# Controller.net
KiCad netlist of a schematic drawn in EAGLE
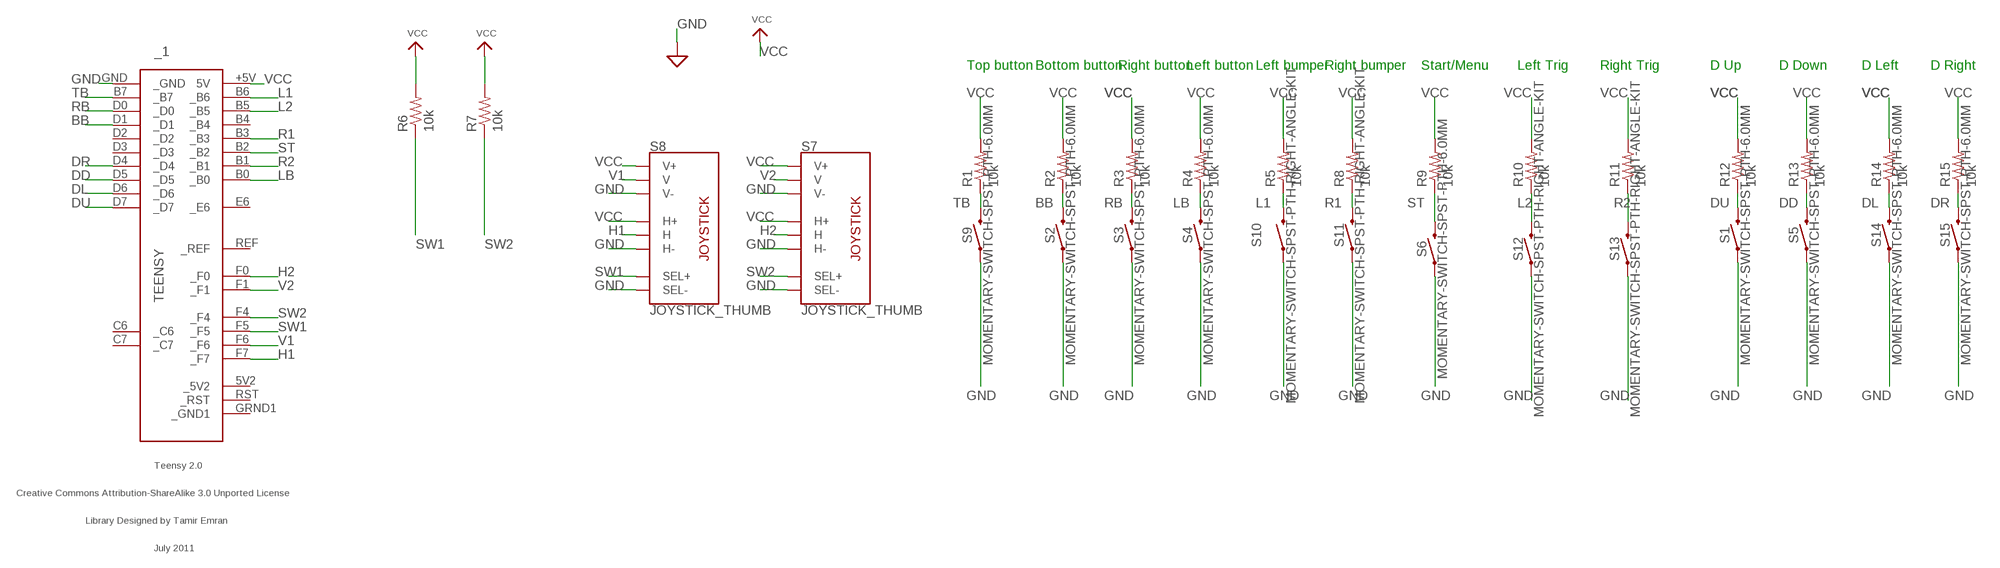
[diagram p0: schematic, sheet 1]

(export (version "E")
  (design (tool "Eeschema 10.0.6"))
  (components
    (comp (ref "R1")
      (value "10k")
      (footprint "eagle-import:0207_10")
      (libsource (lib "eagle-import") (part "R-US_0207/10"))
    )
    (comp (ref "R2")
      (value "10k")
      (footprint "eagle-import:0207_10")
      (libsource (lib "eagle-import") (part "R-US_0207/10"))
    )
    (comp (ref "R3")
      (value "10k")
      (footprint "eagle-import:0207_10")
      (libsource (lib "eagle-import") (part "R-US_0207/10"))
    )
    (comp (ref "R4")
      (value "10k")
      (footprint "eagle-import:0207_10")
      (libsource (lib "eagle-import") (part "R-US_0207/10"))
    )
    (comp (ref "R5")
      (value "10k")
      (footprint "eagle-import:0207_10")
      (libsource (lib "eagle-import") (part "R-US_0207/10"))
    )
    (comp (ref "R6")
      (value "10k")
      (footprint "eagle-import:0207_10")
      (libsource (lib "eagle-import") (part "R-US_0207/10"))
    )
    (comp (ref "R7")
      (value "10k")
      (footprint "eagle-import:0207_10")
      (libsource (lib "eagle-import") (part "R-US_0207/10"))
    )
    (comp (ref "R8")
      (value "10k")
      (footprint "eagle-import:0207_10")
      (libsource (lib "eagle-import") (part "R-US_0207/10"))
    )
    (comp (ref "R9")
      (value "10k")
      (footprint "eagle-import:0207_10")
      (libsource (lib "eagle-import") (part "R-US_0207/10"))
    )
    (comp (ref "R10")
      (value "10k")
      (footprint "eagle-import:0207_10")
      (libsource (lib "eagle-import") (part "R-US_0207/10"))
    )
    (comp (ref "R11")
      (value "10k")
      (footprint "eagle-import:0207_10")
      (libsource (lib "eagle-import") (part "R-US_0207/10"))
    )
    (comp (ref "R12")
      (value "10k")
      (footprint "eagle-import:0207_10")
      (libsource (lib "eagle-import") (part "R-US_0207/10"))
    )
    (comp (ref "R13")
      (value "10k")
      (footprint "eagle-import:0207_10")
      (libsource (lib "eagle-import") (part "R-US_0207/10"))
    )
    (comp (ref "R14")
      (value "10k")
      (footprint "eagle-import:0207_10")
      (libsource (lib "eagle-import") (part "R-US_0207/10"))
    )
    (comp (ref "R15")
      (value "10k")
      (footprint "eagle-import:0207_10")
      (libsource (lib "eagle-import") (part "R-US_0207/10"))
    )
    (comp (ref "S1")
      (value "MOMENTARY-SWITCH-SPST-PTH-6.0MM")
      (footprint "eagle-import:TACTILE_SWITCH_PTH_6.0MM")
      (libsource (lib "eagle-import") (part "MOMENTARY-SWITCH-SPST-PTH-6.0MM"))
    )
    (comp (ref "S2")
      (value "MOMENTARY-SWITCH-SPST-PTH-6.0MM")
      (footprint "eagle-import:TACTILE_SWITCH_PTH_6.0MM")
      (libsource (lib "eagle-import") (part "MOMENTARY-SWITCH-SPST-PTH-6.0MM"))
    )
    (comp (ref "S3")
      (value "MOMENTARY-SWITCH-SPST-PTH-6.0MM")
      (footprint "eagle-import:TACTILE_SWITCH_PTH_6.0MM")
      (libsource (lib "eagle-import") (part "MOMENTARY-SWITCH-SPST-PTH-6.0MM"))
    )
    (comp (ref "S4")
      (value "MOMENTARY-SWITCH-SPST-PTH-6.0MM")
      (footprint "eagle-import:TACTILE_SWITCH_PTH_6.0MM")
      (libsource (lib "eagle-import") (part "MOMENTARY-SWITCH-SPST-PTH-6.0MM"))
    )
    (comp (ref "S5")
      (value "MOMENTARY-SWITCH-SPST-PTH-6.0MM")
      (footprint "eagle-import:TACTILE_SWITCH_PTH_6.0MM")
      (libsource (lib "eagle-import") (part "MOMENTARY-SWITCH-SPST-PTH-6.0MM"))
    )
    (comp (ref "S6")
      (value "MOMENTARY-SWITCH-SPST-PTH-6.0MM")
      (footprint "eagle-import:TACTILE_SWITCH_PTH_6.0MM")
      (libsource (lib "eagle-import") (part "MOMENTARY-SWITCH-SPST-PTH-6.0MM"))
    )
    (comp (ref "S7")
      (value "JOYSTICK_THUMB")
      (footprint "eagle-import:JOYSTICK")
      (libsource (lib "eagle-import") (part "JOYSTICK_THUMB"))
    )
    (comp (ref "S8")
      (value "JOYSTICK_THUMB")
      (footprint "eagle-import:JOYSTICK")
      (libsource (lib "eagle-import") (part "JOYSTICK_THUMB"))
    )
    (comp (ref "S9")
      (value "MOMENTARY-SWITCH-SPST-PTH-6.0MM")
      (footprint "eagle-import:TACTILE_SWITCH_PTH_6.0MM")
      (libsource (lib "eagle-import") (part "MOMENTARY-SWITCH-SPST-PTH-6.0MM"))
    )
    (comp (ref "S10")
      (value "MOMENTARY-SWITCH-SPST-PTH-RIGHT-ANGLE-KIT")
      (footprint "eagle-import:TACTILE_SWITCH_PTH_RIGHT_ANGLE_KIT")
      (libsource (lib "eagle-import") (part "MOMENTARY-SWITCH-SPST-PTH-RIGHT-ANGLE-KIT"))
    )
    (comp (ref "S11")
      (value "MOMENTARY-SWITCH-SPST-PTH-RIGHT-ANGLE-KIT")
      (footprint "eagle-import:TACTILE_SWITCH_PTH_RIGHT_ANGLE_KIT")
      (libsource (lib "eagle-import") (part "MOMENTARY-SWITCH-SPST-PTH-RIGHT-ANGLE-KIT"))
    )
    (comp (ref "S12")
      (value "MOMENTARY-SWITCH-SPST-PTH-RIGHT-ANGLE-KIT")
      (footprint "eagle-import:TACTILE_SWITCH_PTH_RIGHT_ANGLE_KIT")
      (libsource (lib "eagle-import") (part "MOMENTARY-SWITCH-SPST-PTH-RIGHT-ANGLE-KIT"))
    )
    (comp (ref "S13")
      (value "MOMENTARY-SWITCH-SPST-PTH-RIGHT-ANGLE-KIT")
      (footprint "eagle-import:TACTILE_SWITCH_PTH_RIGHT_ANGLE_KIT")
      (libsource (lib "eagle-import") (part "MOMENTARY-SWITCH-SPST-PTH-RIGHT-ANGLE-KIT"))
    )
    (comp (ref "S14")
      (value "MOMENTARY-SWITCH-SPST-PTH-6.0MM")
      (footprint "eagle-import:TACTILE_SWITCH_PTH_6.0MM")
      (libsource (lib "eagle-import") (part "MOMENTARY-SWITCH-SPST-PTH-6.0MM"))
    )
    (comp (ref "S15")
      (value "MOMENTARY-SWITCH-SPST-PTH-6.0MM")
      (footprint "eagle-import:TACTILE_SWITCH_PTH_6.0MM")
      (libsource (lib "eagle-import") (part "MOMENTARY-SWITCH-SPST-PTH-6.0MM"))
    )
    (comp (ref "_1")
      (value "TEENSY")
      (footprint "eagle-import:TEENSY")
      (libsource (lib "eagle-import") (part "TEENSY"))
    )
  )
  (nets
    (net (code "1") (name "/BB") (class "Default")
      (node (ref "R2") (pin "1") (pinfunction "1_1") (pintype "passive"))
      (node (ref "S2") (pin "3") (pinfunction "2_3") (pintype "passive"))
      (node (ref "_1") (pin "D1") (pinfunction "_D1_D1") (pintype "bidirectional"))
    )
    (net (code "2") (name "/DD") (class "Default")
      (node (ref "R13") (pin "1") (pinfunction "1_1") (pintype "passive"))
      (node (ref "S5") (pin "3") (pinfunction "2_3") (pintype "passive"))
      (node (ref "_1") (pin "D5") (pinfunction "_D5_D5") (pintype "bidirectional"))
    )
    (net (code "3") (name "/DL") (class "Default")
      (node (ref "R14") (pin "1") (pinfunction "1_1") (pintype "passive"))
      (node (ref "S14") (pin "3") (pinfunction "2_3") (pintype "passive"))
      (node (ref "_1") (pin "D6") (pinfunction "_D6_D6") (pintype "bidirectional"))
    )
    (net (code "4") (name "/DR") (class "Default")
      (node (ref "R15") (pin "1") (pinfunction "1_1") (pintype "passive"))
      (node (ref "S15") (pin "3") (pinfunction "2_3") (pintype "passive"))
      (node (ref "_1") (pin "D4") (pinfunction "_D4_D4") (pintype "bidirectional"))
    )
    (net (code "5") (name "/DU") (class "Default")
      (node (ref "R12") (pin "1") (pinfunction "1_1") (pintype "passive"))
      (node (ref "S1") (pin "3") (pinfunction "2_3") (pintype "passive"))
      (node (ref "_1") (pin "D7") (pinfunction "_D7_D7") (pintype "bidirectional"))
    )
    (net (code "6") (name "/H1") (class "Default")
      (node (ref "S8") (pin "H2") (pinfunction "H_H2") (pintype "bidirectional"))
      (node (ref "_1") (pin "F7") (pinfunction "_F7_F7") (pintype "bidirectional"))
    )
    (net (code "7") (name "/H2") (class "Default")
      (node (ref "S7") (pin "H2") (pinfunction "H_H2") (pintype "bidirectional"))
      (node (ref "_1") (pin "F0") (pinfunction "_F0_F0") (pintype "bidirectional"))
    )
    (net (code "8") (name "/L1") (class "Default")
      (node (ref "R5") (pin "1") (pinfunction "1_1") (pintype "passive"))
      (node (ref "S10") (pin "2") (pinfunction "2_2") (pintype "passive"))
      (node (ref "_1") (pin "B6") (pinfunction "_B6_B6") (pintype "bidirectional"))
    )
    (net (code "9") (name "/L2") (class "Default")
      (node (ref "R10") (pin "1") (pinfunction "1_1") (pintype "passive"))
      (node (ref "S12") (pin "2") (pinfunction "2_2") (pintype "passive"))
      (node (ref "_1") (pin "B5") (pinfunction "_B5_B5") (pintype "bidirectional"))
    )
    (net (code "10") (name "/LB") (class "Default")
      (node (ref "R4") (pin "1") (pinfunction "1_1") (pintype "passive"))
      (node (ref "S4") (pin "3") (pinfunction "2_3") (pintype "passive"))
      (node (ref "_1") (pin "B0") (pinfunction "_B0_B0") (pintype "bidirectional"))
    )
    (net (code "11") (name "/R1") (class "Default")
      (node (ref "R8") (pin "1") (pinfunction "1_1") (pintype "passive"))
      (node (ref "S11") (pin "2") (pinfunction "2_2") (pintype "passive"))
      (node (ref "_1") (pin "B3") (pinfunction "_B3_B3") (pintype "bidirectional"))
    )
    (net (code "12") (name "/R2") (class "Default")
      (node (ref "R11") (pin "1") (pinfunction "1_1") (pintype "passive"))
      (node (ref "S13") (pin "2") (pinfunction "2_2") (pintype "passive"))
      (node (ref "_1") (pin "B1") (pinfunction "_B1_B1") (pintype "bidirectional"))
    )
    (net (code "13") (name "/RB") (class "Default")
      (node (ref "R3") (pin "1") (pinfunction "1_1") (pintype "passive"))
      (node (ref "S3") (pin "3") (pinfunction "2_3") (pintype "passive"))
      (node (ref "_1") (pin "D0") (pinfunction "_D0_D0") (pintype "bidirectional"))
    )
    (net (code "14") (name "/ST") (class "Default")
      (node (ref "R9") (pin "1") (pinfunction "1_1") (pintype "passive"))
      (node (ref "S6") (pin "3") (pinfunction "2_3") (pintype "passive"))
      (node (ref "_1") (pin "B2") (pinfunction "_B2_B2") (pintype "bidirectional"))
    )
    (net (code "15") (name "/SW1") (class "Default")
      (node (ref "R6") (pin "1") (pinfunction "1_1") (pintype "passive"))
      (node (ref "S8") (pin "B1A") (pinfunction "SEL+_B1A") (pintype "bidirectional"))
      (node (ref "_1") (pin "F5") (pinfunction "_F5_F5") (pintype "bidirectional"))
    )
    (net (code "16") (name "/SW2") (class "Default")
      (node (ref "R7") (pin "1") (pinfunction "1_1") (pintype "passive"))
      (node (ref "S7") (pin "B1A") (pinfunction "SEL+_B1A") (pintype "bidirectional"))
      (node (ref "_1") (pin "F4") (pinfunction "_F4_F4") (pintype "bidirectional"))
    )
    (net (code "17") (name "/TB") (class "Default")
      (node (ref "R1") (pin "1") (pinfunction "1_1") (pintype "passive"))
      (node (ref "S9") (pin "3") (pinfunction "2_3") (pintype "passive"))
      (node (ref "_1") (pin "B7") (pinfunction "_B7_B7") (pintype "bidirectional"))
    )
    (net (code "18") (name "/V1") (class "Default")
      (node (ref "S8") (pin "V2") (pinfunction "V_V2") (pintype "bidirectional"))
      (node (ref "_1") (pin "F6") (pinfunction "_F6_F6") (pintype "bidirectional"))
    )
    (net (code "19") (name "/V2") (class "Default")
      (node (ref "S7") (pin "V2") (pinfunction "V_V2") (pintype "bidirectional"))
      (node (ref "_1") (pin "F1") (pinfunction "_F1_F1") (pintype "bidirectional"))
    )
    (net (code "20") (name "SUP") (class "Default")
      (node (ref "S1") (pin "1") (pinfunction "1_1") (pintype "passive"))
      (node (ref "S10") (pin "1") (pinfunction "1_1") (pintype "passive"))
      (node (ref "S11") (pin "1") (pinfunction "1_1") (pintype "passive"))
      (node (ref "S12") (pin "1") (pinfunction "1_1") (pintype "passive"))
      (node (ref "S13") (pin "1") (pinfunction "1_1") (pintype "passive"))
      (node (ref "S14") (pin "1") (pinfunction "1_1") (pintype "passive"))
      (node (ref "S15") (pin "1") (pinfunction "1_1") (pintype "passive"))
      (node (ref "S2") (pin "1") (pinfunction "1_1") (pintype "passive"))
      (node (ref "S3") (pin "1") (pinfunction "1_1") (pintype "passive"))
      (node (ref "S4") (pin "1") (pinfunction "1_1") (pintype "passive"))
      (node (ref "S5") (pin "1") (pinfunction "1_1") (pintype "passive"))
      (node (ref "S6") (pin "1") (pinfunction "1_1") (pintype "passive"))
      (node (ref "S7") (pin "B2A") (pinfunction "SEL-_B2A") (pintype "bidirectional"))
      (node (ref "S7") (pin "H3") (pinfunction "H-_H3") (pintype "bidirectional"))
      (node (ref "S7") (pin "V3") (pinfunction "V-_V3") (pintype "bidirectional"))
      (node (ref "S8") (pin "B2A") (pinfunction "SEL-_B2A") (pintype "bidirectional"))
      (node (ref "S8") (pin "H3") (pinfunction "H-_H3") (pintype "bidirectional"))
      (node (ref "S8") (pin "V3") (pinfunction "V-_V3") (pintype "bidirectional"))
      (node (ref "S9") (pin "1") (pinfunction "1_1") (pintype "passive"))
      (node (ref "_1") (pin "GND") (pinfunction "_GND_GND") (pintype "bidirectional"))
    )
    (net (code "21") (name "VCC") (class "Default")
      (node (ref "R1") (pin "2") (pinfunction "2_2") (pintype "passive"))
      (node (ref "R10") (pin "2") (pinfunction "2_2") (pintype "passive"))
      (node (ref "R11") (pin "2") (pinfunction "2_2") (pintype "passive"))
      (node (ref "R12") (pin "2") (pinfunction "2_2") (pintype "passive"))
      (node (ref "R13") (pin "2") (pinfunction "2_2") (pintype "passive"))
      (node (ref "R14") (pin "2") (pinfunction "2_2") (pintype "passive"))
      (node (ref "R15") (pin "2") (pinfunction "2_2") (pintype "passive"))
      (node (ref "R2") (pin "2") (pinfunction "2_2") (pintype "passive"))
      (node (ref "R3") (pin "2") (pinfunction "2_2") (pintype "passive"))
      (node (ref "R4") (pin "2") (pinfunction "2_2") (pintype "passive"))
      (node (ref "R5") (pin "2") (pinfunction "2_2") (pintype "passive"))
      (node (ref "R6") (pin "2") (pinfunction "2_2") (pintype "passive"))
      (node (ref "R7") (pin "2") (pinfunction "2_2") (pintype "passive"))
      (node (ref "R8") (pin "2") (pinfunction "2_2") (pintype "passive"))
      (node (ref "R9") (pin "2") (pinfunction "2_2") (pintype "passive"))
      (node (ref "S7") (pin "H1") (pinfunction "H+_H1") (pintype "bidirectional"))
      (node (ref "S7") (pin "V1") (pinfunction "V+_V1") (pintype "bidirectional"))
      (node (ref "S8") (pin "H1") (pinfunction "H+_H1") (pintype "bidirectional"))
      (node (ref "S8") (pin "V1") (pinfunction "V+_V1") (pintype "bidirectional"))
      (node (ref "_1") (pin "+5V") (pinfunction "5V_+5V") (pintype "bidirectional"))
    )
    (net (code "22") (name "unconnected-(_1-_5V2-Pad5V2)") (class "Default")
      (node (ref "_1") (pin "5V2") (pinfunction "_5V2_5V2") (pintype "bidirectional"))
    )
    (net (code "23") (name "unconnected-(_1-_B4-PadB4)") (class "Default")
      (node (ref "_1") (pin "B4") (pinfunction "_B4_B4") (pintype "bidirectional"))
    )
    (net (code "24") (name "unconnected-(_1-_C6-PadC6)") (class "Default")
      (node (ref "_1") (pin "C6") (pinfunction "_C6_C6") (pintype "bidirectional"))
    )
    (net (code "25") (name "unconnected-(_1-_C7-PadC7)") (class "Default")
      (node (ref "_1") (pin "C7") (pinfunction "_C7_C7") (pintype "bidirectional"))
    )
    (net (code "26") (name "unconnected-(_1-_D2-PadD2)") (class "Default")
      (node (ref "_1") (pin "D2") (pinfunction "_D2_D2") (pintype "bidirectional"))
    )
    (net (code "27") (name "unconnected-(_1-_D3-PadD3)") (class "Default")
      (node (ref "_1") (pin "D3") (pinfunction "_D3_D3") (pintype "bidirectional"))
    )
    (net (code "28") (name "unconnected-(_1-_E6-PadE6)") (class "Default")
      (node (ref "_1") (pin "E6") (pinfunction "_E6_E6") (pintype "bidirectional"))
    )
    (net (code "29") (name "unconnected-(_1-_GND1-PadGRND1)") (class "Default")
      (node (ref "_1") (pin "GRND1") (pinfunction "_GND1_GRND1") (pintype "bidirectional"))
    )
    (net (code "30") (name "unconnected-(_1-_REF-PadREF)") (class "Default")
      (node (ref "_1") (pin "REF") (pinfunction "_REF_REF") (pintype "bidirectional"))
    )
    (net (code "31") (name "unconnected-(_1-_RST-PadRST)") (class "Default")
      (node (ref "_1") (pin "RST") (pinfunction "_RST_RST") (pintype "bidirectional"))
    )
  )
)
